# Sheet2.net
KiCad netlist of a schematic drawn in Altium Designer
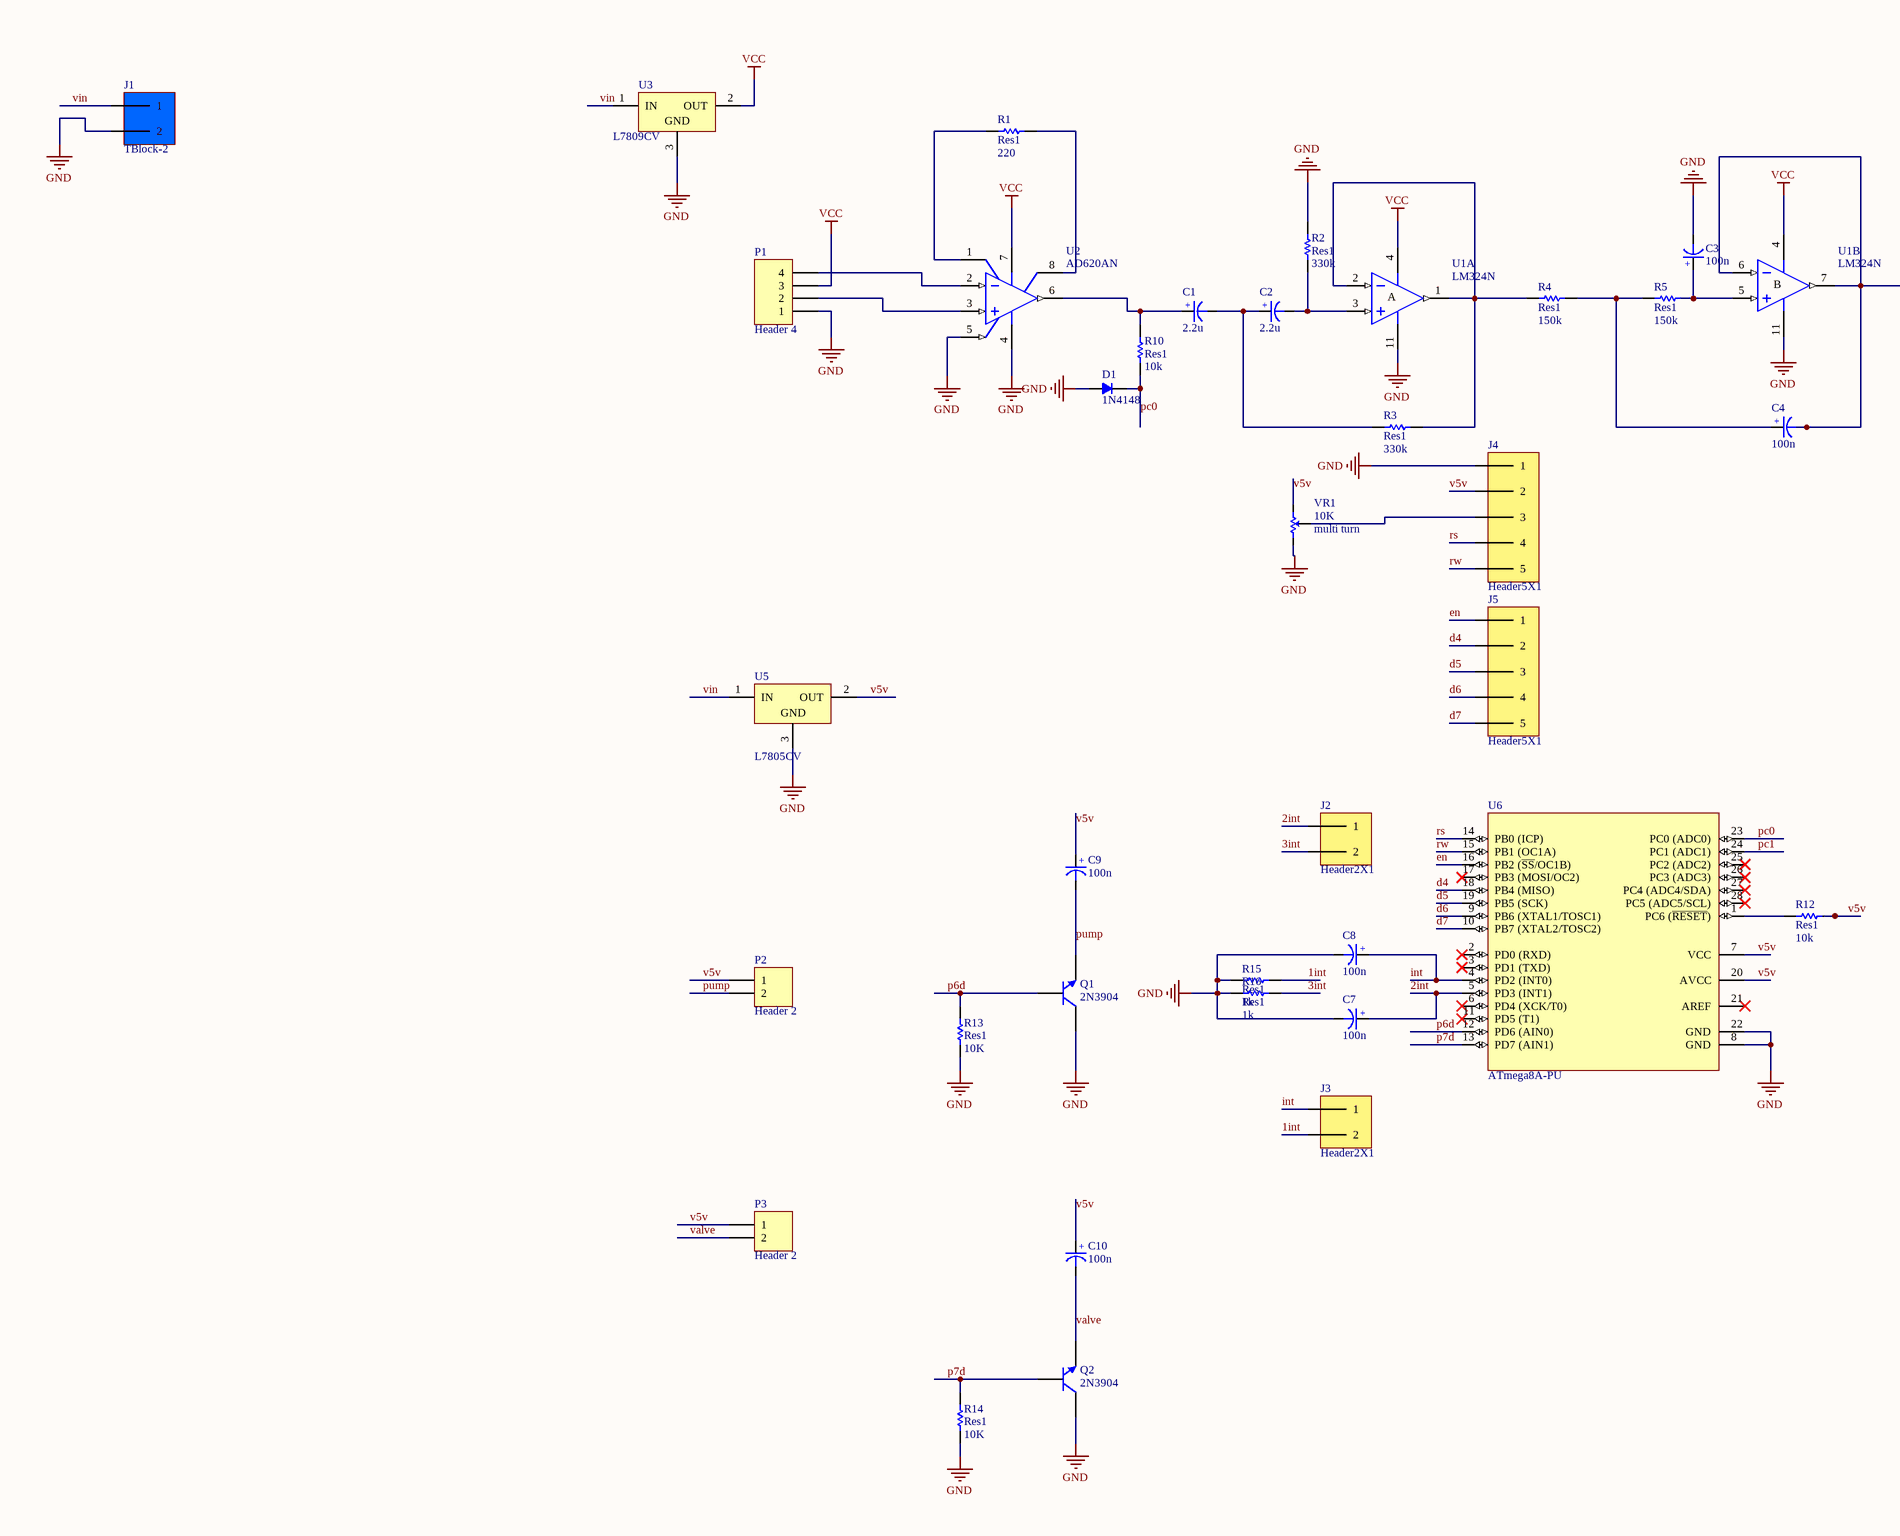
[diagram p0: Sheet2.SchDoc, left]
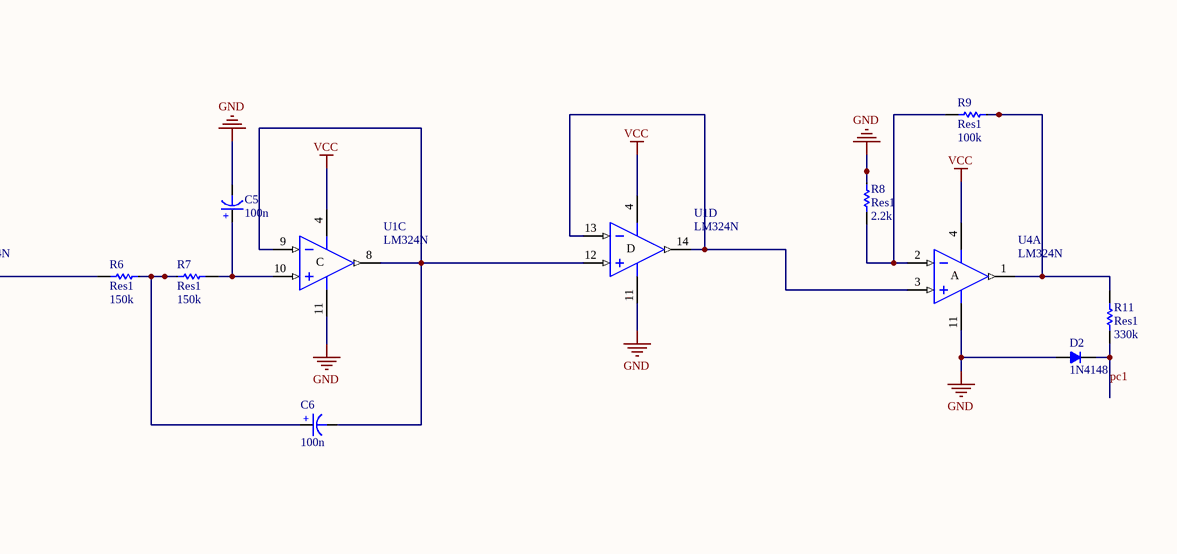
[diagram p1: Sheet2.SchDoc, right]

(export (version "E")
  (design (tool "Eeschema 10.0.6"))
  (components
    (comp (ref "C1")
      (value "2.2u")
      (footprint "ELEC-CAP-RAD10-20")
      (description "Electrolytic Capacitor")
      (libsource (lib "AltiumLib1") (part "Capacitor Electrolytic"))
    )
    (comp (ref "C2")
      (value "2.2u")
      (footprint "ELEC-CAP-RAD10-20")
      (description "Electrolytic Capacitor")
      (libsource (lib "AltiumLib1") (part "Capacitor Electrolytic"))
    )
    (comp (ref "C3")
      (value "100n")
      (footprint "ELEC-CAP-RAD10-20")
      (description "Electrolytic Capacitor")
      (libsource (lib "AltiumLib1") (part "Capacitor Electrolytic"))
    )
    (comp (ref "C4")
      (value "100n")
      (footprint "ELEC-CAP-RAD10-20")
      (description "Electrolytic Capacitor")
      (libsource (lib "AltiumLib1") (part "Capacitor Electrolytic"))
    )
    (comp (ref "C5")
      (value "100n")
      (footprint "ELEC-CAP-RAD10-20")
      (description "Electrolytic Capacitor")
      (libsource (lib "AltiumLib1") (part "Capacitor Electrolytic"))
    )
    (comp (ref "C6")
      (value "100n")
      (footprint "ELEC-CAP-RAD10-20")
      (description "Electrolytic Capacitor")
      (libsource (lib "AltiumLib1") (part "Capacitor Electrolytic"))
    )
    (comp (ref "C7")
      (value "100n")
      (footprint "ELEC-CAP-RAD10-20")
      (description "Electrolytic Capacitor")
      (libsource (lib "") (part "Capacitor Electrolytic_1"))
    )
    (comp (ref "C8")
      (value "100n")
      (footprint "ELEC-CAP-RAD10-20")
      (description "Electrolytic Capacitor")
      (libsource (lib "") (part "Capacitor Electrolytic_1"))
    )
    (comp (ref "C9")
      (value "100n")
      (footprint "ELEC-CAP-RAD10-20")
      (description "Electrolytic Capacitor")
      (libsource (lib "AltiumLib1") (part "Capacitor Electrolytic"))
    )
    (comp (ref "C10")
      (value "100n")
      (footprint "ELEC-CAP-RAD10-20")
      (description "Electrolytic Capacitor")
      (libsource (lib "AltiumLib1") (part "Capacitor Electrolytic"))
    )
    (comp (ref "D1")
      (value "MODEL")
      (footprint "DO-41")
      (description "Diode")
      (fields (field (name "MODEL") "1N4148"))
      (libsource (lib "AltiumLib1") (part "Diode"))
    )
    (comp (ref "D2")
      (value "MODEL")
      (footprint "DO-41")
      (description "Diode")
      (fields (field (name "MODEL") "1N4148"))
      (libsource (lib "AltiumLib1") (part "Diode"))
    )
    (comp (ref "J1")
      (value "TBlock-2")
      (footprint "KF300-2 PIN")
      (libsource (lib "AltiumLib1") (part "TBlock-2"))
    )
    (comp (ref "J2")
      (value "Header2X1")
      (footprint "Header 2X1")
      (libsource (lib "AltiumLib1") (part "Header2X1"))
    )
    (comp (ref "J3")
      (value "Header2X1")
      (footprint "Header 2X1")
      (libsource (lib "AltiumLib1") (part "Header2X1"))
    )
    (comp (ref "J4")
      (value "Header5X1")
      (footprint "HEADER 5X1")
      (libsource (lib "AltiumLib1") (part "Header5X1"))
    )
    (comp (ref "J5")
      (value "Header5X1")
      (footprint "HEADER 5X1")
      (libsource (lib "AltiumLib1") (part "Header5X1"))
    )
    (comp (ref "P1")
      (value "Header 4")
      (footprint "HDR1X4")
      (description "Header, 4-Pin")
      (fields (field (name "PUBLISHER") "Altium Limited"))
      (libsource (lib "Miscellaneous Connectors") (part "Header 4"))
    )
    (comp (ref "P2")
      (value "Header 2")
      (footprint "HDR1X2")
      (description "Header, 2-Pin")
      (fields (field (name "PUBLISHER") "Altium Limited"))
      (libsource (lib "Miscellaneous Connectors") (part "Header 2"))
    )
    (comp (ref "P3")
      (value "Header 2")
      (footprint "HDR1X2")
      (description "Header, 2-Pin")
      (fields (field (name "PUBLISHER") "Altium Limited"))
      (libsource (lib "Miscellaneous Connectors") (part "Header 2"))
    )
    (comp (ref "Q1")
      (value "2N3904")
      (footprint "TO-92A")
      (description "NPN General Purpose Amplifier")
      (fields (field (name "PUBLISHER") "Altium Limited"))
      (libsource (lib "Miscellaneous Devices") (part "2N3904"))
    )
    (comp (ref "Q2")
      (value "2N3904")
      (footprint "TO-92A")
      (description "NPN General Purpose Amplifier")
      (fields (field (name "PUBLISHER") "Altium Limited"))
      (libsource (lib "Miscellaneous Devices") (part "2N3904"))
    )
    (comp (ref "R1")
      (value "Res1")
      (footprint "AXIAL-0.3")
      (description "Resistor")
      (fields (field (name "ALTIUM_VALUE") "220") (field (name "PUBLISHER") "Altium Limited"))
      (libsource (lib "Miscellaneous Devices") (part "Res1"))
    )
    (comp (ref "R2")
      (value "Res1")
      (footprint "AXIAL-0.3")
      (description "Resistor")
      (fields (field (name "ALTIUM_VALUE") "330k") (field (name "PUBLISHER") "Altium Limited"))
      (libsource (lib "Miscellaneous Devices") (part "Res1"))
    )
    (comp (ref "R3")
      (value "Res1")
      (footprint "AXIAL-0.3")
      (description "Resistor")
      (fields (field (name "ALTIUM_VALUE") "330k") (field (name "PUBLISHER") "Altium Limited"))
      (libsource (lib "Miscellaneous Devices") (part "Res1"))
    )
    (comp (ref "R4")
      (value "Res1")
      (footprint "AXIAL-0.3")
      (description "Resistor")
      (fields (field (name "ALTIUM_VALUE") "150k") (field (name "PUBLISHER") "Altium Limited"))
      (libsource (lib "Miscellaneous Devices") (part "Res1"))
    )
    (comp (ref "R5")
      (value "Res1")
      (footprint "AXIAL-0.3")
      (description "Resistor")
      (fields (field (name "ALTIUM_VALUE") "150k") (field (name "PUBLISHER") "Altium Limited"))
      (libsource (lib "Miscellaneous Devices") (part "Res1"))
    )
    (comp (ref "R6")
      (value "Res1")
      (footprint "AXIAL-0.3")
      (description "Resistor")
      (fields (field (name "ALTIUM_VALUE") "150k") (field (name "PUBLISHER") "Altium Limited"))
      (libsource (lib "Miscellaneous Devices") (part "Res1"))
    )
    (comp (ref "R7")
      (value "Res1")
      (footprint "AXIAL-0.3")
      (description "Resistor")
      (fields (field (name "ALTIUM_VALUE") "150k") (field (name "PUBLISHER") "Altium Limited"))
      (libsource (lib "Miscellaneous Devices") (part "Res1"))
    )
    (comp (ref "R8")
      (value "Res1")
      (footprint "AXIAL-0.3")
      (description "Resistor")
      (fields (field (name "ALTIUM_VALUE") "2.2k") (field (name "PUBLISHER") "Altium Limited"))
      (libsource (lib "Miscellaneous Devices") (part "Res1"))
    )
    (comp (ref "R9")
      (value "Res1")
      (footprint "AXIAL-0.3")
      (description "Resistor")
      (fields (field (name "ALTIUM_VALUE") "100k") (field (name "PUBLISHER") "Altium Limited"))
      (libsource (lib "Miscellaneous Devices") (part "Res1"))
    )
    (comp (ref "R10")
      (value "Res1")
      (footprint "AXIAL-0.3")
      (description "Resistor")
      (fields (field (name "ALTIUM_VALUE") "10k") (field (name "PUBLISHER") "Altium Limited"))
      (libsource (lib "Miscellaneous Devices") (part "Res1"))
    )
    (comp (ref "R11")
      (value "Res1")
      (footprint "AXIAL-0.3")
      (description "Resistor")
      (fields (field (name "ALTIUM_VALUE") "330k") (field (name "PUBLISHER") "Altium Limited"))
      (libsource (lib "Miscellaneous Devices") (part "Res1"))
    )
    (comp (ref "R12")
      (value "Res1")
      (footprint "AXIAL-0.3")
      (description "Resistor")
      (fields (field (name "ALTIUM_VALUE") "10k") (field (name "PUBLISHER") "Altium Limited"))
      (libsource (lib "Miscellaneous Devices") (part "Res1"))
    )
    (comp (ref "R13")
      (value "Res1")
      (footprint "AXIAL-0.3")
      (description "Resistor")
      (fields (field (name "ALTIUM_VALUE") "10K") (field (name "PUBLISHER") "Altium Limited"))
      (libsource (lib "Miscellaneous Devices") (part "Res1"))
    )
    (comp (ref "R14")
      (value "Res1")
      (footprint "AXIAL-0.3")
      (description "Resistor")
      (fields (field (name "ALTIUM_VALUE") "10K") (field (name "PUBLISHER") "Altium Limited"))
      (libsource (lib "Miscellaneous Devices") (part "Res1"))
    )
    (comp (ref "R15")
      (value "Res1")
      (footprint "AXIAL-0.3")
      (description "Resistor")
      (fields (field (name "ALTIUM_VALUE") "1k") (field (name "PUBLISHER") "Altium Limited"))
      (libsource (lib "Miscellaneous Devices") (part "Res1"))
    )
    (comp (ref "R16")
      (value "Res1")
      (footprint "AXIAL-0.3")
      (description "Resistor")
      (fields (field (name "ALTIUM_VALUE") "1k") (field (name "PUBLISHER") "Altium Limited"))
      (libsource (lib "Miscellaneous Devices") (part "Res1"))
    )
    (comp (ref "U1")
      (value "LM324N")
      (footprint "DIP14")
      (description "Low-Power Quad Operational Amplifier")
      (fields (field (name "PUBLISHER") "Altium Limited"))
      (libsource (lib "ST Operational Amplifier") (part "LM324N"))
    )
    (comp (ref "U2")
      (value "AD620AN")
      (footprint "N-8")
      (description "Low-Cost, Low-Power Instrumentation Amplifier")
      (fields (field (name "PUBLISHER") "Altium Limited"))
      (libsource (lib "AD Instrumentation Amplifier") (part "AD620AN"))
    )
    (comp (ref "U3")
      (value "L7809CV")
      (footprint "TO220ABN")
      (description "Positive Voltage Regulator")
      (fields (field (name "PUBLISHER") "Altium Limited"))
      (libsource (lib "ST Power Mgt Voltage Regulator") (part "L7809CV"))
    )
    (comp (ref "U4")
      (value "LM324N")
      (footprint "DIP14")
      (description "Low-Power Quad Operational Amplifier")
      (fields (field (name "PUBLISHER") "Altium Limited"))
      (libsource (lib "ST Operational Amplifier") (part "LM324N"))
    )
    (comp (ref "U5")
      (value "L7805CV")
      (footprint "TO220ABN")
      (description "Positive Voltage Regulator")
      (fields (field (name "PUBLISHER") "Altium Limited"))
      (libsource (lib "ST Power Mgt Voltage Regulator") (part "L7805CV"))
    )
    (comp (ref "U6")
      (value "ATmega8A-PU")
      (footprint "28P3")
      (fields (field (name "PUBLISHER") "Altium Limited"))
      (libsource (lib "Atmel Microcontroller 8-Bit megaAVR") (part "ATmega8A-PU"))
    )
    (comp (ref "VR1")
      (value "10K")
      (footprint "Multi Turn")
      (description "Variable Resistor")
      (fields (field (name "TYPE") "multi turn"))
      (libsource (lib "AltiumLib1") (part "Resistor Variable"))
    )
  )
  (nets
    (net (code "1") (name "/1int") (class "Default")
      (node (ref "J3") (pin "2") (pinfunction "2_2") (pintype "passive"))
      (node (ref "R15") (pin "1") (pinfunction "1_1") (pintype "passive"))
    )
    (net (code "2") (name "/2int") (class "Default")
      (node (ref "C7") (pin "2") (pinfunction "+_2") (pintype "passive"))
      (node (ref "J2") (pin "1") (pinfunction "1_1") (pintype "passive"))
      (node (ref "U6") (pin "5") (pinfunction "PD3_(INT1)_5") (pintype "bidirectional"))
    )
    (net (code "3") (name "/3int") (class "Default")
      (node (ref "J2") (pin "2") (pinfunction "2_2") (pintype "passive"))
      (node (ref "R16") (pin "1") (pinfunction "1_1") (pintype "passive"))
    )
    (net (code "4") (name "/d4") (class "Default")
      (node (ref "J5") (pin "2") (pinfunction "2_2") (pintype "passive"))
      (node (ref "U6") (pin "18") (pinfunction "PB4_(MISO)_18") (pintype "bidirectional"))
    )
    (net (code "5") (name "/d5") (class "Default")
      (node (ref "J5") (pin "3") (pinfunction "3_3") (pintype "passive"))
      (node (ref "U6") (pin "19") (pinfunction "PB5_(SCK)_19") (pintype "bidirectional"))
    )
    (net (code "6") (name "/d6") (class "Default")
      (node (ref "J5") (pin "4") (pinfunction "4_4") (pintype "passive"))
      (node (ref "U6") (pin "9") (pinfunction "PB6_(XTAL1/TOSC1)_9") (pintype "bidirectional"))
    )
    (net (code "7") (name "/d7") (class "Default")
      (node (ref "J5") (pin "5") (pinfunction "5_5") (pintype "passive"))
      (node (ref "U6") (pin "10") (pinfunction "PB7_(XTAL2/TOSC2)_10") (pintype "bidirectional"))
    )
    (net (code "8") (name "/en") (class "Default")
      (node (ref "J5") (pin "1") (pinfunction "1_1") (pintype "passive"))
      (node (ref "U6") (pin "16") (pinfunction "PB2_(~{SS}/OC1B)_16") (pintype "bidirectional"))
    )
    (net (code "9") (name "/int") (class "Default")
      (node (ref "C8") (pin "2") (pinfunction "+_2") (pintype "passive"))
      (node (ref "J3") (pin "1") (pinfunction "1_1") (pintype "passive"))
      (node (ref "U6") (pin "4") (pinfunction "PD2_(INT0)_4") (pintype "bidirectional"))
    )
    (net (code "10") (name "/p6d") (class "Default")
      (node (ref "Q1") (pin "2") (pinfunction "B_2") (pintype "passive"))
      (node (ref "R13") (pin "2") (pinfunction "2_2") (pintype "passive"))
      (node (ref "U6") (pin "12") (pinfunction "PD6_(AIN0)_12") (pintype "bidirectional"))
    )
    (net (code "11") (name "/p7d") (class "Default")
      (node (ref "Q2") (pin "2") (pinfunction "B_2") (pintype "passive"))
      (node (ref "R14") (pin "2") (pinfunction "2_2") (pintype "passive"))
      (node (ref "U6") (pin "13") (pinfunction "PD7_(AIN1)_13") (pintype "bidirectional"))
    )
    (net (code "12") (name "/pc0") (class "Default")
      (node (ref "D1") (pin "2") (pinfunction "K_2") (pintype "passive"))
      (node (ref "R10") (pin "1") (pinfunction "1_1") (pintype "passive"))
      (node (ref "U6") (pin "23") (pinfunction "PC0_(ADC0)_23") (pintype "bidirectional"))
    )
    (net (code "13") (name "/pc1") (class "Default")
      (node (ref "D2") (pin "2") (pinfunction "K_2") (pintype "passive"))
      (node (ref "R11") (pin "1") (pinfunction "1_1") (pintype "passive"))
      (node (ref "U6") (pin "24") (pinfunction "PC1_(ADC1)_24") (pintype "bidirectional"))
    )
    (net (code "14") (name "/pump") (class "Default")
      (node (ref "C9") (pin "1") (pinfunction "-_1") (pintype "passive"))
      (node (ref "P2") (pin "2") (pinfunction "2_2") (pintype "passive"))
      (node (ref "Q1") (pin "1") (pinfunction "E_1") (pintype "passive"))
    )
    (net (code "15") (name "/rs") (class "Default")
      (node (ref "J4") (pin "4") (pinfunction "4_4") (pintype "passive"))
      (node (ref "U6") (pin "14") (pinfunction "PB0_(ICP)_14") (pintype "bidirectional"))
    )
    (net (code "16") (name "/rw") (class "Default")
      (node (ref "J4") (pin "5") (pinfunction "5_5") (pintype "passive"))
      (node (ref "U6") (pin "15") (pinfunction "PB1_(OC1A)_15") (pintype "bidirectional"))
    )
    (net (code "17") (name "/v5v") (class "Default")
      (node (ref "C10") (pin "2") (pinfunction "+_2") (pintype "passive"))
      (node (ref "C9") (pin "2") (pinfunction "+_2") (pintype "passive"))
      (node (ref "J4") (pin "2") (pinfunction "2_2") (pintype "passive"))
      (node (ref "P2") (pin "1") (pinfunction "1_1") (pintype "passive"))
      (node (ref "P3") (pin "1") (pinfunction "1_1") (pintype "passive"))
      (node (ref "R12") (pin "1") (pinfunction "1_1") (pintype "passive"))
      (node (ref "U5") (pin "2") (pinfunction "OUT_2") (pintype "power_in"))
      (node (ref "U6") (pin "20") (pinfunction "AVCC_20") (pintype "power_in"))
      (node (ref "U6") (pin "7") (pinfunction "VCC_7") (pintype "power_in"))
      (node (ref "VR1") (pin "3") (pinfunction "CW_3") (pintype "passive"))
    )
    (net (code "18") (name "/valve") (class "Default")
      (node (ref "C10") (pin "1") (pinfunction "-_1") (pintype "passive"))
      (node (ref "P3") (pin "2") (pinfunction "2_2") (pintype "passive"))
      (node (ref "Q2") (pin "1") (pinfunction "E_1") (pintype "passive"))
    )
    (net (code "19") (name "/vin") (class "Default")
      (node (ref "J1") (pin "1") (pinfunction "1_1") (pintype "passive"))
      (node (ref "U3") (pin "1") (pinfunction "IN_1") (pintype "power_in"))
      (node (ref "U5") (pin "1") (pinfunction "IN_1") (pintype "power_in"))
    )
    (net (code "20") (name "GND") (class "Default")
      (node (ref "C3") (pin "1") (pinfunction "-_1") (pintype "passive"))
      (node (ref "C5") (pin "1") (pinfunction "-_1") (pintype "passive"))
      (node (ref "C7") (pin "1") (pinfunction "-_1") (pintype "passive"))
      (node (ref "C8") (pin "1") (pinfunction "-_1") (pintype "passive"))
      (node (ref "D1") (pin "1") (pinfunction "A_1") (pintype "passive"))
      (node (ref "D2") (pin "1") (pinfunction "A_1") (pintype "passive"))
      (node (ref "J1") (pin "2") (pinfunction "2_2") (pintype "passive"))
      (node (ref "J4") (pin "1") (pinfunction "1_1") (pintype "passive"))
      (node (ref "P1") (pin "1") (pinfunction "1_1") (pintype "passive"))
      (node (ref "Q1") (pin "3") (pinfunction "C_3") (pintype "passive"))
      (node (ref "Q2") (pin "3") (pinfunction "C_3") (pintype "passive"))
      (node (ref "R13") (pin "1") (pinfunction "1_1") (pintype "passive"))
      (node (ref "R14") (pin "1") (pinfunction "1_1") (pintype "passive"))
      (node (ref "R15") (pin "2") (pinfunction "2_2") (pintype "passive"))
      (node (ref "R16") (pin "2") (pinfunction "2_2") (pintype "passive"))
      (node (ref "R2") (pin "2") (pinfunction "2_2") (pintype "passive"))
      (node (ref "R8") (pin "1") (pinfunction "1_1") (pintype "passive"))
      (node (ref "U1") (pin "11") (pinfunction "V-_11") (pintype "power_in"))
      (node (ref "U2") (pin "4") (pinfunction "V-_4") (pintype "power_in"))
      (node (ref "U2") (pin "5") (pinfunction "REF_5") (pintype "input"))
      (node (ref "U3") (pin "3") (pinfunction "GND_3") (pintype "power_in"))
      (node (ref "U4") (pin "11") (pinfunction "V-_11") (pintype "power_in"))
      (node (ref "U5") (pin "3") (pinfunction "GND_3") (pintype "power_in"))
      (node (ref "U6") (pin "22") (pinfunction "GND_22") (pintype "power_in"))
      (node (ref "U6") (pin "8") (pinfunction "GND_8") (pintype "power_in"))
      (node (ref "VR1") (pin "1") (pinfunction "CCW_1") (pintype "passive"))
    )
    (net (code "21") (name "Net-(C1-+)") (class "Default")
      (node (ref "C1") (pin "2") (pinfunction "+_2") (pintype "passive"))
      (node (ref "R10") (pin "2") (pinfunction "2_2") (pintype "passive"))
      (node (ref "U2") (pin "6") (pinfunction "OUT_6") (pintype "output"))
    )
    (net (code "22") (name "Net-(C1--)") (class "Default")
      (node (ref "C1") (pin "1") (pinfunction "-_1") (pintype "passive"))
      (node (ref "C2") (pin "2") (pinfunction "+_2") (pintype "passive"))
      (node (ref "R3") (pin "2") (pinfunction "2_2") (pintype "passive"))
    )
    (net (code "23") (name "Net-(C2--)") (class "Default")
      (node (ref "C2") (pin "1") (pinfunction "-_1") (pintype "passive"))
      (node (ref "R2") (pin "1") (pinfunction "1_1") (pintype "passive"))
      (node (ref "U1") (pin "3") (pinfunction "IN+_3") (pintype "input"))
    )
    (net (code "24") (name "Net-(C3-+)") (class "Default")
      (node (ref "C3") (pin "2") (pinfunction "+_2") (pintype "passive"))
      (node (ref "R5") (pin "1") (pinfunction "1_1") (pintype "passive"))
      (node (ref "U1") (pin "5") (pinfunction "IN+_5") (pintype "input"))
    )
    (net (code "25") (name "Net-(C4-+)") (class "Default")
      (node (ref "C4") (pin "2") (pinfunction "+_2") (pintype "passive"))
      (node (ref "R4") (pin "1") (pinfunction "1_1") (pintype "passive"))
      (node (ref "R5") (pin "2") (pinfunction "2_2") (pintype "passive"))
    )
    (net (code "26") (name "Net-(C4--)") (class "Default")
      (node (ref "C4") (pin "1") (pinfunction "-_1") (pintype "passive"))
      (node (ref "R6") (pin "2") (pinfunction "2_2") (pintype "passive"))
      (node (ref "U1") (pin "6") (pinfunction "IN-_6") (pintype "input"))
      (node (ref "U1") (pin "7") (pinfunction "OUT_7") (pintype "output"))
    )
    (net (code "27") (name "Net-(C5-+)") (class "Default")
      (node (ref "C5") (pin "2") (pinfunction "+_2") (pintype "passive"))
      (node (ref "R7") (pin "1") (pinfunction "1_1") (pintype "passive"))
      (node (ref "U1") (pin "10") (pinfunction "IN+_10") (pintype "input"))
    )
    (net (code "28") (name "Net-(C6-+)") (class "Default")
      (node (ref "C6") (pin "2") (pinfunction "+_2") (pintype "passive"))
      (node (ref "R6") (pin "1") (pinfunction "1_1") (pintype "passive"))
      (node (ref "R7") (pin "2") (pinfunction "2_2") (pintype "passive"))
    )
    (net (code "29") (name "Net-(C6--)") (class "Default")
      (node (ref "C6") (pin "1") (pinfunction "-_1") (pintype "passive"))
      (node (ref "U1") (pin "12") (pinfunction "IN+_12") (pintype "input"))
      (node (ref "U1") (pin "8") (pinfunction "OUT_8") (pintype "output"))
      (node (ref "U1") (pin "9") (pinfunction "IN-_9") (pintype "input"))
    )
    (net (code "30") (name "Net-(R1-Pad1)") (class "Default")
      (node (ref "R1") (pin "1") (pinfunction "1_1") (pintype "passive"))
      (node (ref "U2") (pin "1") (pinfunction "RG_1") (pintype "passive"))
    )
    (net (code "31") (name "Net-(R1-Pad2)") (class "Default")
      (node (ref "R1") (pin "2") (pinfunction "2_2") (pintype "passive"))
      (node (ref "U2") (pin "8") (pinfunction "RG_8") (pintype "passive"))
    )
    (net (code "32") (name "Net-(U1A-IN-)") (class "Default")
      (node (ref "R3") (pin "1") (pinfunction "1_1") (pintype "passive"))
      (node (ref "R4") (pin "2") (pinfunction "2_2") (pintype "passive"))
      (node (ref "U1") (pin "1") (pinfunction "OUT_1") (pintype "output"))
      (node (ref "U1") (pin "2") (pinfunction "IN-_2") (pintype "input"))
    )
    (net (code "33") (name "Net-(U1D-IN-)") (class "Default")
      (node (ref "U1") (pin "13") (pinfunction "IN-_13") (pintype "input"))
      (node (ref "U1") (pin "14") (pinfunction "OUT_14") (pintype "output"))
      (node (ref "U4") (pin "3") (pinfunction "IN+_3") (pintype "input"))
    )
    (net (code "34") (name "Net-(U2-+IN)") (class "Default")
      (node (ref "P1") (pin "2") (pinfunction "2_2") (pintype "passive"))
      (node (ref "U2") (pin "3") (pinfunction "+IN_3") (pintype "input"))
    )
    (net (code "35") (name "Net-(U2--IN)") (class "Default")
      (node (ref "P1") (pin "4") (pinfunction "4_4") (pintype "passive"))
      (node (ref "U2") (pin "2") (pinfunction "-IN_2") (pintype "input"))
    )
    (net (code "36") (name "Net-(U4A-IN-)") (class "Default")
      (node (ref "R8") (pin "2") (pinfunction "2_2") (pintype "passive"))
      (node (ref "R9") (pin "2") (pinfunction "2_2") (pintype "passive"))
      (node (ref "U4") (pin "2") (pinfunction "IN-_2") (pintype "input"))
    )
    (net (code "37") (name "Net-(U4A-OUT)") (class "Default")
      (node (ref "R11") (pin "2") (pinfunction "2_2") (pintype "passive"))
      (node (ref "R9") (pin "1") (pinfunction "1_1") (pintype "passive"))
      (node (ref "U4") (pin "1") (pinfunction "OUT_1") (pintype "output"))
    )
    (net (code "38") (name "Net-(U6-PC6_(~{RESET}))") (class "Default")
      (node (ref "R12") (pin "2") (pinfunction "2_2") (pintype "passive"))
      (node (ref "U6") (pin "1") (pinfunction "PC6_(~{RESET})_1") (pintype "bidirectional"))
    )
    (net (code "39") (name "Net-(VR1-Setpoint)") (class "Default")
      (node (ref "J4") (pin "3") (pinfunction "3_3") (pintype "passive"))
      (node (ref "VR1") (pin "2") (pinfunction "Setpoint_2") (pintype "passive"))
    )
    (net (code "40") (name "VCC") (class "Default")
      (node (ref "P1") (pin "3") (pinfunction "3_3") (pintype "passive"))
      (node (ref "U1") (pin "4") (pinfunction "V+_4") (pintype "power_in"))
      (node (ref "U2") (pin "7") (pinfunction "V+_7") (pintype "power_in"))
      (node (ref "U3") (pin "2") (pinfunction "OUT_2") (pintype "power_in"))
      (node (ref "U4") (pin "4") (pinfunction "V+_4") (pintype "power_in"))
    )
    (net (code "41") (name "unconnected-(U6-AREF-Pad21)") (class "Default")
      (node (ref "U6") (pin "21") (pinfunction "AREF_21") (pintype "passive+no_connect"))
    )
    (net (code "42") (name "unconnected-(U6-PB3_(MOSI{slash}OC2)-Pad17)") (class "Default")
      (node (ref "U6") (pin "17") (pinfunction "PB3_(MOSI/OC2)_17") (pintype "bidirectional+no_connect"))
    )
    (net (code "43") (name "unconnected-(U6-PC2_(ADC2)-Pad25)") (class "Default")
      (node (ref "U6") (pin "25") (pinfunction "PC2_(ADC2)_25") (pintype "bidirectional+no_connect"))
    )
    (net (code "44") (name "unconnected-(U6-PC3_(ADC3)-Pad26)") (class "Default")
      (node (ref "U6") (pin "26") (pinfunction "PC3_(ADC3)_26") (pintype "bidirectional+no_connect"))
    )
    (net (code "45") (name "unconnected-(U6-PC4_(ADC4{slash}SDA)-Pad27)") (class "Default")
      (node (ref "U6") (pin "27") (pinfunction "PC4_(ADC4/SDA)_27") (pintype "bidirectional+no_connect"))
    )
    (net (code "46") (name "unconnected-(U6-PC5_(ADC5{slash}SCL)-Pad28)") (class "Default")
      (node (ref "U6") (pin "28") (pinfunction "PC5_(ADC5/SCL)_28") (pintype "bidirectional+no_connect"))
    )
    (net (code "47") (name "unconnected-(U6-PD0_(RXD)-Pad2)") (class "Default")
      (node (ref "U6") (pin "2") (pinfunction "PD0_(RXD)_2") (pintype "bidirectional+no_connect"))
    )
    (net (code "48") (name "unconnected-(U6-PD1_(TXD)-Pad3)") (class "Default")
      (node (ref "U6") (pin "3") (pinfunction "PD1_(TXD)_3") (pintype "bidirectional+no_connect"))
    )
    (net (code "49") (name "unconnected-(U6-PD4_(XCK{slash}T0)-Pad6)") (class "Default")
      (node (ref "U6") (pin "6") (pinfunction "PD4_(XCK/T0)_6") (pintype "bidirectional+no_connect"))
    )
    (net (code "50") (name "unconnected-(U6-PD5_(T1)-Pad11)") (class "Default")
      (node (ref "U6") (pin "11") (pinfunction "PD5_(T1)_11") (pintype "bidirectional+no_connect"))
    )
  )
)
